# Ethernet_Sheet.net
KiCad netlist of a schematic drawn in Altium Designer
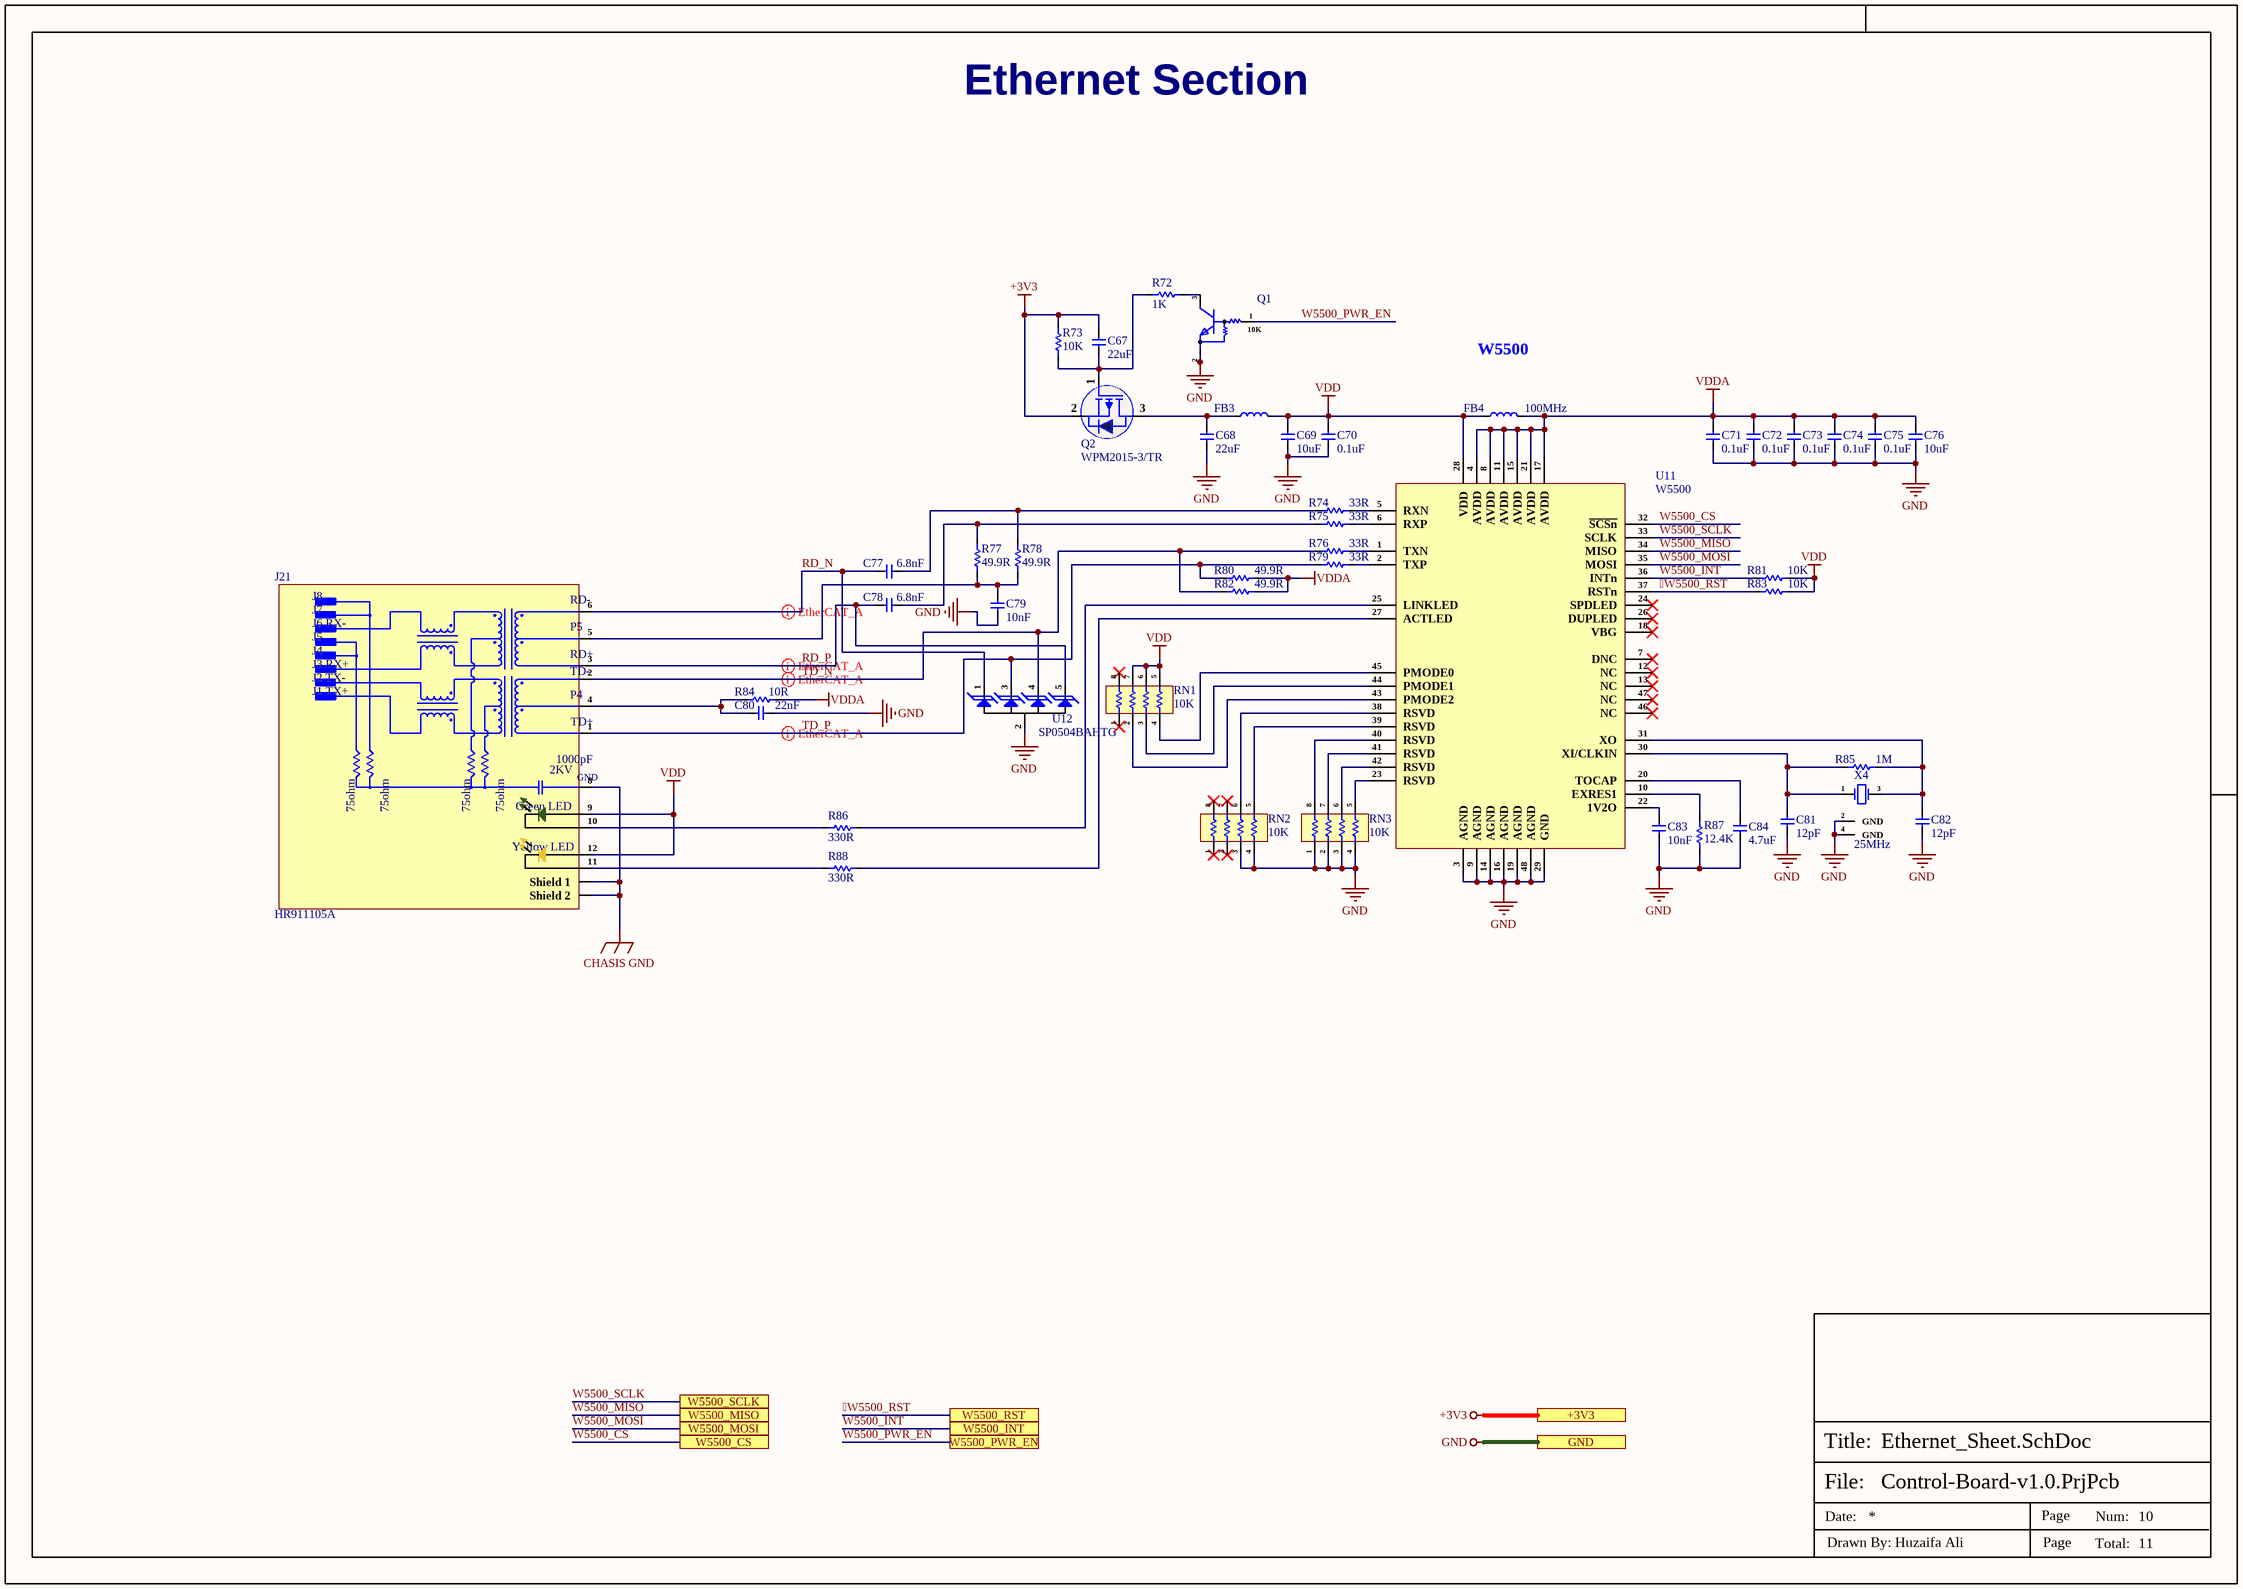
[diagram p0: Ethernet_Sheet.SchDoc]

(export (version "E")
  (design (tool "Eeschema 10.0.6"))
  (components
    (comp (ref "C67")
      (value "22uF")
      (footprint "Cap-0805")
      (description "CAP CER 22UF 35V X5R 0805")
      (fields
        (field (name "MANUFACTURER") "TDK Corporation")
        (field (name "MANUFACTURER PART NUMBER") "C2012X5R1V226MT000E")
      )
      (libsource (lib "eSpark Libraries") (part "C2012X5R1V226MT000E"))
    )
    (comp (ref "C68")
      (value "22uF")
      (footprint "Cap-0805")
      (description "CAP CER 22UF 25V X5R 0805")
      (fields
        (field (name "MANUFACTURER") "Yageo")
        (field (name "MANUFACTURER PART NUMBER") "CC0805MKX5R8BB226")
      )
      (libsource (lib "eSpark Libraries") (part "CC0805MKX5R8BB226"))
    )
    (comp (ref "C69")
      (value "10uF")
      (footprint "Cap-0603")
      (description "CAP CER 10UF 16V X5R 0603")
      (fields
        (field (name "MANUFACTURER") "Yageo")
        (field (name "MANUFACTURER PART NUMBER") "CC0603KRX5R7BB106")
      )
      (libsource (lib "eSpark Libraries") (part "CC0603KRX5R7BB106"))
    )
    (comp (ref "C70")
      (value "0.1uF")
      (footprint "Cap-0402")
      (description "CAP CER 0.1UF 50V X5R 0402")
      (fields
        (field (name "MANUFACTURER") "TDK")
        (field (name "MANUFACTURER PART NUMBER") "C1005X5R1H104K050BB")
      )
      (libsource (lib "eSpark Libraries") (part "C1005X5R1H104K050BB"))
    )
    (comp (ref "C71")
      (value "0.1uF")
      (footprint "Cap-0402")
      (description "CAP CER 0.1UF 50V X5R 0402")
      (fields
        (field (name "MANUFACTURER") "TDK")
        (field (name "MANUFACTURER PART NUMBER") "C1005X5R1H104K050BB")
      )
      (libsource (lib "eSpark Libraries") (part "C1005X5R1H104K050BB"))
    )
    (comp (ref "C72")
      (value "0.1uF")
      (footprint "Cap-0402")
      (description "CAP CER 0.1UF 50V X5R 0402")
      (fields
        (field (name "MANUFACTURER") "TDK")
        (field (name "MANUFACTURER PART NUMBER") "C1005X5R1H104K050BB")
      )
      (libsource (lib "eSpark Libraries") (part "C1005X5R1H104K050BB"))
    )
    (comp (ref "C73")
      (value "0.1uF")
      (footprint "Cap-0402")
      (description "CAP CER 0.1UF 50V X5R 0402")
      (fields
        (field (name "MANUFACTURER") "TDK")
        (field (name "MANUFACTURER PART NUMBER") "C1005X5R1H104K050BB")
      )
      (libsource (lib "eSpark Libraries") (part "C1005X5R1H104K050BB"))
    )
    (comp (ref "C74")
      (value "0.1uF")
      (footprint "Cap-0402")
      (description "CAP CER 0.1UF 50V X5R 0402")
      (fields
        (field (name "MANUFACTURER") "TDK")
        (field (name "MANUFACTURER PART NUMBER") "C1005X5R1H104K050BB")
      )
      (libsource (lib "eSpark Libraries") (part "C1005X5R1H104K050BB"))
    )
    (comp (ref "C75")
      (value "0.1uF")
      (footprint "Cap-0402")
      (description "CAP CER 0.1UF 50V X5R 0402")
      (fields
        (field (name "MANUFACTURER") "TDK")
        (field (name "MANUFACTURER PART NUMBER") "C1005X5R1H104K050BB")
      )
      (libsource (lib "eSpark Libraries") (part "C1005X5R1H104K050BB"))
    )
    (comp (ref "C76")
      (value "10uF")
      (footprint "Cap-0603")
      (description "CAP CER 10UF 16V X5R 0603")
      (fields
        (field (name "MANUFACTURER") "Yageo")
        (field (name "MANUFACTURER PART NUMBER") "CC0603KRX5R7BB106")
      )
      (libsource (lib "eSpark Libraries") (part "CC0603KRX5R7BB106"))
    )
    (comp (ref "C77")
      (value "6.8nF")
      (footprint "Cap-0603")
      (description "50V 6.8nF X7R ±10% 0603")
      (fields (field (name "MANUFACTURER") "FH") (field (name "MANUFACTURER PART NUMBER") "0603B682K500NT"))
      (libsource (lib "eSpark Libraries") (part "0603B682K500NT"))
    )
    (comp (ref "C78")
      (value "6.8nF")
      (footprint "Cap-0603")
      (description "50V 6.8nF X7R ±10% 0603")
      (fields (field (name "MANUFACTURER") "FH") (field (name "MANUFACTURER PART NUMBER") "0603B682K500NT"))
      (libsource (lib "eSpark Libraries") (part "0603B682K500NT"))
    )
    (comp (ref "C79")
      (value "10nF")
      (footprint "Cap-0603")
      (description "CAP CER 10000PF 50V C0G/NPO 0603")
      (fields
        (field (name "MANUFACTURER") "Yageo")
        (field (name "MANUFACTURER PART NUMBER") "CC0603JRNPO9BN103")
      )
      (libsource (lib "eSpark Libraries") (part "CC0603JRNPO9BN103"))
    )
    (comp (ref "C80")
      (value "22nF")
      (footprint "Cap-0603")
      (description "CAP CER 0.022UF 50V X7R 0603")
      (fields
        (field (name "MANUFACTURER") "Yageo")
        (field (name "MANUFACTURER PART NUMBER") "CC0603KRX7R9BB223")
      )
      (libsource (lib "eSpark Libraries") (part "CC0603KRX7R9BB223"))
    )
    (comp (ref "C81")
      (value "12pF")
      (footprint "Cap-0603")
      (description "CAP CER 12PF 50V C0G/NPO 0603")
      (fields
        (field (name "MANUFACTURER") "Yageo")
        (field (name "MANUFACTURER PART NUMBER") "CC0603J*NPO9B*120")
      )
      (libsource (lib "eSpark Libraries") (part "CC0603JRNPO9BN120"))
    )
    (comp (ref "C82")
      (value "12pF")
      (footprint "Cap-0603")
      (description "CAP CER 12PF 50V C0G/NPO 0603")
      (fields
        (field (name "MANUFACTURER") "Yageo")
        (field (name "MANUFACTURER PART NUMBER") "CC0603J*NPO9B*120")
      )
      (libsource (lib "eSpark Libraries") (part "CC0603JRNPO9BN120"))
    )
    (comp (ref "C83")
      (value "10nF")
      (footprint "Cap-0603")
      (description "CAP CER 10000PF 50V C0G/NPO 0603")
      (fields
        (field (name "MANUFACTURER") "Yageo")
        (field (name "MANUFACTURER PART NUMBER") "CC0603JRNPO9BN103")
      )
      (libsource (lib "eSpark Libraries") (part "CC0603JRNPO9BN103"))
    )
    (comp (ref "C84")
      (value "4.7uF")
      (footprint "Cap-0603")
      (description "CAP CER 4.7UF 10V X5R 0603")
      (fields
        (field (name "MANUFACTURER") "Yageo")
        (field (name "MANUFACTURER PART NUMBER") "CC0603KRX5R6BB475")
      )
      (libsource (lib "eSpark Libraries") (part "CC0603KRX5R6BB475"))
    )
    (comp (ref "FB3")
      (value "100MHz")
      (footprint "Ind-0805")
      (description "100mΩ ±25% 300Ω@100MHz 0805 Ferrite Beads ROHS")
      (fields
        (field (name "MANUFACTURER") "YJYCOIN")
        (field (name "MANUFACTURER PART NUMBER") "YI201209U301-2R0T")
      )
      (libsource (lib "eSpark Libraries") (part "YI201209U301-2R0T"))
    )
    (comp (ref "FB4")
      (value "100MHz")
      (footprint "Ind-0805")
      (description "100mΩ ±25% 300Ω@100MHz 0805 Ferrite Beads ROHS")
      (fields
        (field (name "MANUFACTURER") "YJYCOIN")
        (field (name "MANUFACTURER PART NUMBER") "YI201209U301-2R0T")
      )
      (libsource (lib "eSpark Libraries") (part "YI201209U301-2R0T"))
    )
    (comp (ref "J21")
      (value "HR911105A")
      (footprint "HR911105A")
      (description "RJ45 RJReceptacle 1 WithLED Plugin Ethernet Connectors/Modular Connectors (RJ45 RJ11) ROHS")
      (fields (field (name "MANUFACTURER") "HANRUN") (field (name "LCSC PART NUMBER") "C12074"))
      (libsource (lib "eSpark Libraries") (part "HR911105A"))
    )
    (comp (ref "Q1")
      (value "LMUN2211LT1G")
      (footprint "SOT-23")
      (description "NPN 246mW 100mA 50V SOT-23 Digital Transistors ROHS")
      (fields (field (name "MANUFACTURER") "LRC") (field (name "LCSC PART NUMBER") "C12775"))
      (libsource (lib "eSpark Libraries") (part "LMUN2211LT1G"))
    )
    (comp (ref "Q2")
      (value "WPM2015-3/TR")
      (footprint "Sot-23")
      (description "20V 2.2A 800mW 110mΩ@4.5V,2.7A 810mV@250uA P Channel SOT-23 MOSFETs ROHS")
      (fields (field (name "MANUFACTURER") "WILLSEMI") (field (name "LCSC PART NUMBER") "C213159"))
      (libsource (lib "eSpark Libraries") (part "WPM2015-3/TR"))
    )
    (comp (ref "R72")
      (value "1K")
      (footprint "Res-0402")
      (description "RES SMD 1K OHM 1% 1/5W 0402")
      (fields
        (field (name "MANUFACTURER") "Vishay Dale")
        (field (name "MANUFACTURER PART NUMBER") "CRCW04021K00FKEDHP")
      )
      (libsource (lib "eSpark Libraries") (part "CRCW04021K00FKEDHP"))
    )
    (comp (ref "R73")
      (value "10K")
      (footprint "Res-0402")
      (description "RES 10K OHM 1% 1/16W 0402")
      (fields
        (field (name "MANUFACTURER") "Yageo")
        (field (name "MANUFACTURER PART NUMBER") "RC0402FR-0710KL")
      )
      (libsource (lib "eSpark Libraries") (part "RC0402FR-0710KL"))
    )
    (comp (ref "R74")
      (value "33R")
      (footprint "Res-0402")
      (description "RES 33 OHM 1% 1/16W 0402")
      (fields
        (field (name "MANUFACTURER") "Yageo")
        (field (name "MANUFACTURER PART NUMBER") "RC0402FR-0733RL")
      )
      (libsource (lib "eSpark Libraries") (part "RC0402FR-0733RL"))
    )
    (comp (ref "R75")
      (value "33R")
      (footprint "Res-0402")
      (description "RES 33 OHM 1% 1/16W 0402")
      (fields
        (field (name "MANUFACTURER") "Yageo")
        (field (name "MANUFACTURER PART NUMBER") "RC0402FR-0733RL")
      )
      (libsource (lib "eSpark Libraries") (part "RC0402FR-0733RL"))
    )
    (comp (ref "R76")
      (value "33R")
      (footprint "Res-0402")
      (description "RES 33 OHM 1% 1/16W 0402")
      (fields
        (field (name "MANUFACTURER") "Yageo")
        (field (name "MANUFACTURER PART NUMBER") "RC0402FR-0733RL")
      )
      (libsource (lib "eSpark Libraries") (part "RC0402FR-0733RL"))
    )
    (comp (ref "R77")
      (value "49.9R")
      (footprint "Res-0603")
      (description "RES 49.9 OHM 1% 1/10W 0603")
      (fields
        (field (name "MANUFACTURER") "Yageo")
        (field (name "MANUFACTURER PART NUMBER") "RC0603FR-0749R9L")
      )
      (libsource (lib "eSpark Libraries") (part "RC0603FR-0749R9L"))
    )
    (comp (ref "R78")
      (value "49.9R")
      (footprint "Res-0603")
      (description "RES 49.9 OHM 1% 1/10W 0603")
      (fields
        (field (name "MANUFACTURER") "Yageo")
        (field (name "MANUFACTURER PART NUMBER") "RC0603FR-0749R9L")
      )
      (libsource (lib "eSpark Libraries") (part "RC0603FR-0749R9L"))
    )
    (comp (ref "R79")
      (value "33R")
      (footprint "Res-0402")
      (description "RES 33 OHM 1% 1/16W 0402")
      (fields
        (field (name "MANUFACTURER") "Yageo")
        (field (name "MANUFACTURER PART NUMBER") "RC0402FR-0733RL")
      )
      (libsource (lib "eSpark Libraries") (part "RC0402FR-0733RL"))
    )
    (comp (ref "R80")
      (value "49.9R")
      (footprint "Res-0603")
      (description "RES 49.9 OHM 1% 1/10W 0603")
      (fields
        (field (name "MANUFACTURER") "Yageo")
        (field (name "MANUFACTURER PART NUMBER") "RC0603FR-0749R9L")
      )
      (libsource (lib "eSpark Libraries") (part "RC0603FR-0749R9L"))
    )
    (comp (ref "R81")
      (value "10K")
      (footprint "Res-0402")
      (description "RES 10K OHM 1% 1/16W 0402")
      (fields
        (field (name "MANUFACTURER") "Yageo")
        (field (name "MANUFACTURER PART NUMBER") "RC0402FR-0710KL")
      )
      (libsource (lib "eSpark Libraries") (part "RC0402FR-0710KL"))
    )
    (comp (ref "R82")
      (value "49.9R")
      (footprint "Res-0603")
      (description "RES 49.9 OHM 1% 1/10W 0603")
      (fields
        (field (name "MANUFACTURER") "Yageo")
        (field (name "MANUFACTURER PART NUMBER") "RC0603FR-0749R9L")
      )
      (libsource (lib "eSpark Libraries") (part "RC0603FR-0749R9L"))
    )
    (comp (ref "R83")
      (value "10K")
      (footprint "Res-0402")
      (description "RES 10K OHM 1% 1/16W 0402")
      (fields
        (field (name "MANUFACTURER") "Yageo")
        (field (name "MANUFACTURER PART NUMBER") "RC0402FR-0710KL")
      )
      (libsource (lib "eSpark Libraries") (part "RC0402FR-0710KL"))
    )
    (comp (ref "R84")
      (value "10R")
      (footprint "Res-0402")
      (description "RES SMD 10 OHM 1% 1/5W 0402")
      (fields
        (field (name "MANUFACTURER") "Vishay Dale")
        (field (name "MANUFACTURER PART NUMBER") "CRCW040210R0FKEDHP")
      )
      (libsource (lib "eSpark Libraries") (part "CRCW040210R0FKEDHP"))
    )
    (comp (ref "R85")
      (value "1M")
      (footprint "Res-0402")
      (description "RES SMD 1M OHM 5% 1/16W 0402")
      (fields
        (field (name "MANUFACTURER") "Yageo")
        (field (name "MANUFACTURER PART NUMBER") "AF0402JR-071ML")
      )
      (libsource (lib "eSpark Libraries") (part "AF0402JR-071ML"))
    )
    (comp (ref "R86")
      (value "330R")
      (footprint "Res-0402")
      (description "SMD Chip Resistor, 330 Ohm, ± 1%, 63 mW, 0402 [1005 Metric], Thick Film, General Purpose")
      (fields
        (field (name "MANUFACTURER") "Vishay Semiconductors")
        (field (name "MANUFACTURER PART NUMBER") "CRCW0402330RFKEDC")
      )
      (libsource (lib "eSpark Libraries") (part "CRCW0402330RFKEDC"))
    )
    (comp (ref "R87")
      (value "12.4K")
      (footprint "Res-0603")
      (description "RES SMD 12.4K OHM 1% 1/10W 0603")
      (fields
        (field (name "MANUFACTURER") "Yageo")
        (field (name "MANUFACTURER PART NUMBER") "RC0603FR-0712K4L")
      )
      (libsource (lib "eSpark Libraries") (part "RC0603FR-0712K4L"))
    )
    (comp (ref "R88")
      (value "330R")
      (footprint "Res-0402")
      (description "SMD Chip Resistor, 330 Ohm, ± 1%, 63 mW, 0402 [1005 Metric], Thick Film, General Purpose")
      (fields
        (field (name "MANUFACTURER") "Vishay Semiconductors")
        (field (name "MANUFACTURER PART NUMBER") "CRCW0402330RFKEDC")
      )
      (libsource (lib "eSpark Libraries") (part "CRCW0402330RFKEDC"))
    )
    (comp (ref "RN1")
      (value "10K")
      (footprint "YC164-FR-0710KL")
      (description "RES ARRAY 4 RES 10K OHM 1206")
      (fields
        (field (name "MANUFACTURER") "Yageo")
        (field (name "MANUFACTURER PART NUMBER") "YC164-FR-0710KL")
      )
      (libsource (lib "eSpark Libraries") (part "YC164-FR-0710KL"))
    )
    (comp (ref "RN2")
      (value "10K")
      (footprint "YC164-FR-0710KL")
      (description "RES ARRAY 4 RES 10K OHM 1206")
      (fields
        (field (name "MANUFACTURER") "Yageo")
        (field (name "MANUFACTURER PART NUMBER") "YC164-FR-0710KL")
      )
      (libsource (lib "eSpark Libraries") (part "YC164-FR-0710KL"))
    )
    (comp (ref "RN3")
      (value "10K")
      (footprint "YC164-FR-0710KL")
      (description "RES ARRAY 4 RES 10K OHM 1206")
      (fields
        (field (name "MANUFACTURER") "Yageo")
        (field (name "MANUFACTURER PART NUMBER") "YC164-FR-0710KL")
      )
      (libsource (lib "eSpark Libraries") (part "YC164-FR-0710KL"))
    )
    (comp (ref "U11")
      (value "W5500")
      (footprint "48-LQFP (7x7)_")
      (description "SPI LQFP-48(7x7) Ethernet ICs ROHS")
      (fields (field (name "MANUFACTURER") "WIZNET") (field (name "LCSC PART NUMBER") "C32843"))
      (libsource (lib "eSpark Libraries") (part "W5500"))
    )
    (comp (ref "U12")
      (value "SP0504BAHTG")
      (footprint "SOT-23-5")
      (description "TVS DIODE 5.5VWM 8.5VC SOT23-5")
      (fields (field (name "MANUFACTURER") "Littelfuse") (field (name "LCSC PART NUMBER") "C10675"))
      (libsource (lib "eSpark Libraries") (part "SP0504BAHTG"))
    )
    (comp (ref "X4")
      (value "25MHz")
      (footprint "Q22FA12800090")
      (description "CRYSTAL 25.0000MHZ 12PF SMD")
      (fields
        (field (name "MANUFACTURER") "Seiko Epson")
        (field (name "MANUFACTURER PART NUMBER") "Q22FA12800090")
      )
      (libsource (lib "eSpark Libraries") (part "Q22FA12800090"))
    )
  )
  (nets
    (net (code "1") (name "+3V3") (class "Default")
      (node (ref "C67") (pin "2") (pinfunction "2_2") (pintype "passive"))
      (node (ref "Q2") (pin "2") (pinfunction "S_2") (pintype "passive"))
      (node (ref "R73") (pin "2") (pinfunction "2_2") (pintype "passive"))
    )
    (net (code "2") (name "/W5500_RST") (class "Default")
      (node (ref "R83") (pin "2") (pinfunction "2_2") (pintype "passive"))
      (node (ref "U11") (pin "37") (pinfunction "RSTn_37") (pintype "passive"))
    )
    (net (code "3") (name "/RD_N") (class "Default")
      (node (ref "C77") (pin "1") (pinfunction "1_1") (pintype "passive"))
      (node (ref "J21") (pin "6") (pinfunction "RD-_6") (pintype "passive"))
      (node (ref "U12") (pin "1") (pinfunction "K_1") (pintype "passive"))
    )
    (net (code "4") (name "/RD_P") (class "Default")
      (node (ref "C78") (pin "1") (pinfunction "1_1") (pintype "passive"))
      (node (ref "J21") (pin "3") (pinfunction "RD+_3") (pintype "passive"))
      (node (ref "U12") (pin "5") (pinfunction "K_5") (pintype "passive"))
    )
    (net (code "5") (name "/TD_N") (class "Default")
      (node (ref "J21") (pin "2") (pinfunction "TD-_2") (pintype "passive"))
      (node (ref "R76") (pin "1") (pinfunction "1_1") (pintype "passive"))
      (node (ref "R82") (pin "2") (pinfunction "2_2") (pintype "passive"))
      (node (ref "U12") (pin "4") (pinfunction "K_4") (pintype "passive"))
    )
    (net (code "6") (name "/TD_P") (class "Default")
      (node (ref "J21") (pin "1") (pinfunction "TD+_1") (pintype "passive"))
      (node (ref "R79") (pin "1") (pinfunction "1_1") (pintype "passive"))
      (node (ref "R80") (pin "2") (pinfunction "2_2") (pintype "passive"))
      (node (ref "U12") (pin "3") (pinfunction "K_3") (pintype "passive"))
    )
    (net (code "7") (name "/W5500_CS") (class "Default")
      (node (ref "U11") (pin "32") (pinfunction "~{SCSn}_32") (pintype "passive"))
    )
    (net (code "8") (name "/W5500_INT") (class "Default")
      (node (ref "R81") (pin "2") (pinfunction "2_2") (pintype "passive"))
      (node (ref "U11") (pin "36") (pinfunction "INTn_36") (pintype "passive"))
    )
    (net (code "9") (name "/W5500_MISO") (class "Default")
      (node (ref "U11") (pin "34") (pinfunction "MISO_34") (pintype "passive"))
    )
    (net (code "10") (name "/W5500_MOSI") (class "Default")
      (node (ref "U11") (pin "35") (pinfunction "MOSI_35") (pintype "passive"))
    )
    (net (code "11") (name "/W5500_PWR_EN") (class "Default")
      (node (ref "Q1") (pin "1") (pinfunction "B_1") (pintype "passive"))
    )
    (net (code "12") (name "/W5500_SCLK") (class "Default")
      (node (ref "U11") (pin "33") (pinfunction "SCLK_33") (pintype "passive"))
    )
    (net (code "13") (name "CHASIS GND") (class "Default")
      (node (ref "J21") (pin "8") (pinfunction "GND_8") (pintype "power_in"))
      (node (ref "J21") (pin "Shield_1") (pinfunction "Shield_1_Shield_1") (pintype "passive"))
      (node (ref "J21") (pin "Shield_2") (pinfunction "Shield_2_Shield_2") (pintype "passive"))
    )
    (net (code "14") (name "GND") (class "Default")
      (node (ref "C68") (pin "1") (pinfunction "1_1") (pintype "passive"))
      (node (ref "C69") (pin "1") (pinfunction "1_1") (pintype "passive"))
      (node (ref "C70") (pin "1") (pinfunction "1_1") (pintype "passive"))
      (node (ref "C71") (pin "1") (pinfunction "1_1") (pintype "passive"))
      (node (ref "C72") (pin "1") (pinfunction "1_1") (pintype "passive"))
      (node (ref "C73") (pin "1") (pinfunction "1_1") (pintype "passive"))
      (node (ref "C74") (pin "1") (pinfunction "1_1") (pintype "passive"))
      (node (ref "C75") (pin "1") (pinfunction "1_1") (pintype "passive"))
      (node (ref "C76") (pin "1") (pinfunction "1_1") (pintype "passive"))
      (node (ref "C79") (pin "1") (pinfunction "1_1") (pintype "passive"))
      (node (ref "C80") (pin "2") (pinfunction "2_2") (pintype "passive"))
      (node (ref "C81") (pin "1") (pinfunction "1_1") (pintype "passive"))
      (node (ref "C82") (pin "1") (pinfunction "1_1") (pintype "passive"))
      (node (ref "C83") (pin "1") (pinfunction "1_1") (pintype "passive"))
      (node (ref "C84") (pin "1") (pinfunction "1_1") (pintype "passive"))
      (node (ref "Q1") (pin "2") (pinfunction "E_2") (pintype "passive"))
      (node (ref "R87") (pin "1") (pinfunction "1_1") (pintype "passive"))
      (node (ref "RN2") (pin "3") (pintype "passive"))
      (node (ref "RN2") (pin "4") (pintype "passive"))
      (node (ref "RN3") (pin "1") (pintype "passive"))
      (node (ref "RN3") (pin "2") (pintype "passive"))
      (node (ref "RN3") (pin "3") (pintype "passive"))
      (node (ref "RN3") (pin "4") (pintype "passive"))
      (node (ref "U11") (pin "14") (pinfunction "AGND_14") (pintype "passive"))
      (node (ref "U11") (pin "16") (pinfunction "AGND_16") (pintype "passive"))
      (node (ref "U11") (pin "19") (pinfunction "AGND_19") (pintype "passive"))
      (node (ref "U11") (pin "29") (pinfunction "GND_29") (pintype "passive"))
      (node (ref "U11") (pin "3") (pinfunction "AGND_3") (pintype "passive"))
      (node (ref "U11") (pin "48") (pinfunction "AGND_48") (pintype "passive"))
      (node (ref "U11") (pin "9") (pinfunction "AGND_9") (pintype "passive"))
      (node (ref "U12") (pin "2") (pinfunction "A_2") (pintype "passive"))
      (node (ref "X4") (pin "2") (pinfunction "GND_2") (pintype "passive"))
      (node (ref "X4") (pin "4") (pinfunction "GND_4") (pintype "passive"))
    )
    (net (code "15") (name "Net-(C77-Pad2)") (class "Default")
      (node (ref "C77") (pin "2") (pinfunction "2_2") (pintype "passive"))
      (node (ref "R74") (pin "1") (pinfunction "1_1") (pintype "passive"))
      (node (ref "R78") (pin "2") (pinfunction "2_2") (pintype "passive"))
    )
    (net (code "16") (name "Net-(C78-Pad2)") (class "Default")
      (node (ref "C78") (pin "2") (pinfunction "2_2") (pintype "passive"))
      (node (ref "R75") (pin "1") (pinfunction "1_1") (pintype "passive"))
      (node (ref "R77") (pin "2") (pinfunction "2_2") (pintype "passive"))
    )
    (net (code "17") (name "Net-(J21-CATHODE-Pad10)") (class "Default")
      (node (ref "J21") (pin "10") (pinfunction "CATHODE_10") (pintype "passive"))
      (node (ref "R86") (pin "1") (pinfunction "1_1") (pintype "passive"))
    )
    (net (code "18") (name "Net-(J21-CATHODE-Pad11)") (class "Default")
      (node (ref "J21") (pin "11") (pinfunction "CATHODE_11") (pintype "passive"))
      (node (ref "R88") (pin "1") (pinfunction "1_1") (pintype "passive"))
    )
    (net (code "19") (name "Net-(J21-P4)") (class "Default")
      (node (ref "C80") (pin "1") (pinfunction "1_1") (pintype "passive"))
      (node (ref "J21") (pin "4") (pinfunction "P4_4") (pintype "passive"))
      (node (ref "R84") (pin "1") (pinfunction "1_1") (pintype "passive"))
    )
    (net (code "20") (name "Net-(J21-P5)") (class "Default")
      (node (ref "C79") (pin "2") (pinfunction "2_2") (pintype "passive"))
      (node (ref "J21") (pin "5") (pinfunction "P5_5") (pintype "passive"))
      (node (ref "R77") (pin "1") (pinfunction "1_1") (pintype "passive"))
      (node (ref "R78") (pin "1") (pinfunction "1_1") (pintype "passive"))
    )
    (net (code "21") (name "Net-(Q1-C)") (class "Default")
      (node (ref "Q1") (pin "3") (pinfunction "C_3") (pintype "passive"))
      (node (ref "R72") (pin "2") (pinfunction "2_2") (pintype "passive"))
    )
    (net (code "22") (name "Net-(Q2-D)") (class "Default")
      (node (ref "C68") (pin "2") (pinfunction "2_2") (pintype "passive"))
      (node (ref "FB3") (pin "1") (pinfunction "1_1") (pintype "passive"))
      (node (ref "Q2") (pin "3") (pinfunction "D_3") (pintype "passive"))
    )
    (net (code "23") (name "Net-(Q2-G)") (class "Default")
      (node (ref "C67") (pin "1") (pinfunction "1_1") (pintype "passive"))
      (node (ref "Q2") (pin "1") (pinfunction "G_1") (pintype "passive"))
      (node (ref "R72") (pin "1") (pinfunction "1_1") (pintype "passive"))
      (node (ref "R73") (pin "1") (pinfunction "1_1") (pintype "passive"))
    )
    (net (code "24") (name "Net-(RN2-Pad5)") (class "Default")
      (node (ref "RN2") (pin "5") (pintype "passive"))
      (node (ref "U11") (pin "39") (pinfunction "RSVD_39") (pintype "passive"))
    )
    (net (code "25") (name "Net-(RN2-Pad6)") (class "Default")
      (node (ref "RN2") (pin "6") (pintype "passive"))
      (node (ref "U11") (pin "38") (pinfunction "RSVD_38") (pintype "passive"))
    )
    (net (code "26") (name "Net-(RN3-Pad5)") (class "Default")
      (node (ref "RN3") (pin "5") (pintype "passive"))
      (node (ref "U11") (pin "23") (pinfunction "RSVD_23") (pintype "passive"))
    )
    (net (code "27") (name "Net-(RN3-Pad6)") (class "Default")
      (node (ref "RN3") (pin "6") (pintype "passive"))
      (node (ref "U11") (pin "42") (pinfunction "RSVD_42") (pintype "passive"))
    )
    (net (code "28") (name "Net-(RN3-Pad7)") (class "Default")
      (node (ref "RN3") (pin "7") (pintype "passive"))
      (node (ref "U11") (pin "41") (pinfunction "RSVD_41") (pintype "passive"))
    )
    (net (code "29") (name "Net-(RN3-Pad8)") (class "Default")
      (node (ref "RN3") (pin "8") (pintype "passive"))
      (node (ref "U11") (pin "40") (pinfunction "RSVD_40") (pintype "passive"))
    )
    (net (code "30") (name "Net-(U11-1V2O)") (class "Default")
      (node (ref "C83") (pin "2") (pinfunction "2_2") (pintype "passive"))
      (node (ref "U11") (pin "22") (pinfunction "1V2O_22") (pintype "passive"))
    )
    (net (code "31") (name "Net-(U11-ACTLED)") (class "Default")
      (node (ref "R88") (pin "2") (pinfunction "2_2") (pintype "passive"))
      (node (ref "U11") (pin "27") (pinfunction "ACTLED_27") (pintype "passive"))
    )
    (net (code "32") (name "Net-(U11-EXRES1)") (class "Default")
      (node (ref "R87") (pin "2") (pinfunction "2_2") (pintype "passive"))
      (node (ref "U11") (pin "10") (pinfunction "EXRES1_10") (pintype "passive"))
    )
    (net (code "33") (name "Net-(U11-LINKLED)") (class "Default")
      (node (ref "R86") (pin "2") (pinfunction "2_2") (pintype "passive"))
      (node (ref "U11") (pin "25") (pinfunction "LINKLED_25") (pintype "passive"))
    )
    (net (code "34") (name "Net-(U11-PMODE0)") (class "Default")
      (node (ref "RN1") (pin "4") (pintype "passive"))
      (node (ref "U11") (pin "45") (pinfunction "PMODE0_45") (pintype "passive"))
    )
    (net (code "35") (name "Net-(U11-PMODE1)") (class "Default")
      (node (ref "RN1") (pin "3") (pintype "passive"))
      (node (ref "U11") (pin "44") (pinfunction "PMODE1_44") (pintype "passive"))
    )
    (net (code "36") (name "Net-(U11-PMODE2)") (class "Default")
      (node (ref "RN1") (pin "2") (pintype "passive"))
      (node (ref "U11") (pin "43") (pinfunction "PMODE2_43") (pintype "passive"))
    )
    (net (code "37") (name "Net-(U11-RXN)") (class "Default")
      (node (ref "R74") (pin "2") (pinfunction "2_2") (pintype "passive"))
      (node (ref "U11") (pin "5") (pinfunction "RXN_5") (pintype "passive"))
    )
    (net (code "38") (name "Net-(U11-RXP)") (class "Default")
      (node (ref "R75") (pin "2") (pinfunction "2_2") (pintype "passive"))
      (node (ref "U11") (pin "6") (pinfunction "RXP_6") (pintype "passive"))
    )
    (net (code "39") (name "Net-(U11-TOCAP)") (class "Default")
      (node (ref "C84") (pin "2") (pinfunction "2_2") (pintype "passive"))
      (node (ref "U11") (pin "20") (pinfunction "TOCAP_20") (pintype "passive"))
    )
    (net (code "40") (name "Net-(U11-TXN)") (class "Default")
      (node (ref "R76") (pin "2") (pinfunction "2_2") (pintype "passive"))
      (node (ref "U11") (pin "1") (pinfunction "TXN_1") (pintype "passive"))
    )
    (net (code "41") (name "Net-(U11-TXP)") (class "Default")
      (node (ref "R79") (pin "2") (pinfunction "2_2") (pintype "passive"))
      (node (ref "U11") (pin "2") (pinfunction "TXP_2") (pintype "passive"))
    )
    (net (code "42") (name "Net-(U11-XI{slash}CLKIN)") (class "Default")
      (node (ref "C81") (pin "2") (pinfunction "2_2") (pintype "passive"))
      (node (ref "R85") (pin "1") (pinfunction "1_1") (pintype "passive"))
      (node (ref "U11") (pin "30") (pinfunction "XI/CLKIN_30") (pintype "passive"))
      (node (ref "X4") (pin "1") (pinfunction "OSC1_1") (pintype "passive"))
    )
    (net (code "43") (name "Net-(U11-XO)") (class "Default")
      (node (ref "C82") (pin "2") (pinfunction "2_2") (pintype "passive"))
      (node (ref "R85") (pin "2") (pinfunction "2_2") (pintype "passive"))
      (node (ref "U11") (pin "31") (pinfunction "XO_31") (pintype "passive"))
      (node (ref "X4") (pin "3") (pinfunction "OSC2_3") (pintype "passive"))
    )
    (net (code "44") (name "VDD") (class "Default")
      (node (ref "C69") (pin "2") (pinfunction "2_2") (pintype "passive"))
      (node (ref "C70") (pin "2") (pinfunction "2_2") (pintype "passive"))
      (node (ref "FB3") (pin "2") (pinfunction "2_2") (pintype "passive"))
      (node (ref "FB4") (pin "1") (pinfunction "1_1") (pintype "passive"))
      (node (ref "J21") (pin "12") (pinfunction "ANODE_12") (pintype "passive"))
      (node (ref "J21") (pin "9") (pinfunction "ANODE_9") (pintype "passive"))
      (node (ref "R81") (pin "1") (pinfunction "1_1") (pintype "passive"))
      (node (ref "R83") (pin "1") (pinfunction "1_1") (pintype "passive"))
      (node (ref "RN1") (pin "5") (pintype "passive"))
      (node (ref "RN1") (pin "6") (pintype "passive"))
      (node (ref "RN1") (pin "7") (pintype "passive"))
      (node (ref "U11") (pin "28") (pinfunction "VDD_28") (pintype "passive"))
    )
    (net (code "45") (name "VDDA") (class "Default")
      (node (ref "C71") (pin "2") (pinfunction "2_2") (pintype "passive"))
      (node (ref "C72") (pin "2") (pinfunction "2_2") (pintype "passive"))
      (node (ref "C73") (pin "2") (pinfunction "2_2") (pintype "passive"))
      (node (ref "C74") (pin "2") (pinfunction "2_2") (pintype "passive"))
      (node (ref "C75") (pin "2") (pinfunction "2_2") (pintype "passive"))
      (node (ref "C76") (pin "2") (pinfunction "2_2") (pintype "passive"))
      (node (ref "FB4") (pin "2") (pinfunction "2_2") (pintype "passive"))
      (node (ref "R80") (pin "1") (pinfunction "1_1") (pintype "passive"))
      (node (ref "R82") (pin "1") (pinfunction "1_1") (pintype "passive"))
      (node (ref "R84") (pin "2") (pinfunction "2_2") (pintype "passive"))
      (node (ref "U11") (pin "11") (pinfunction "AVDD_11") (pintype "passive"))
      (node (ref "U11") (pin "15") (pinfunction "AVDD_15") (pintype "passive"))
      (node (ref "U11") (pin "17") (pinfunction "AVDD_17") (pintype "passive"))
      (node (ref "U11") (pin "21") (pinfunction "AVDD_21") (pintype "passive"))
      (node (ref "U11") (pin "4") (pinfunction "AVDD_4") (pintype "passive"))
      (node (ref "U11") (pin "8") (pinfunction "AVDD_8") (pintype "passive"))
    )
    (net (code "46") (name "unconnected-(RN1-Pad1)") (class "Default")
      (node (ref "RN1") (pin "1") (pintype "passive+no_connect"))
    )
    (net (code "47") (name "unconnected-(RN1-Pad8)") (class "Default")
      (node (ref "RN1") (pin "8") (pintype "passive+no_connect"))
    )
    (net (code "48") (name "unconnected-(RN2-Pad1)") (class "Default")
      (node (ref "RN2") (pin "1") (pintype "passive+no_connect"))
    )
    (net (code "49") (name "unconnected-(RN2-Pad2)") (class "Default")
      (node (ref "RN2") (pin "2") (pintype "passive+no_connect"))
    )
    (net (code "50") (name "unconnected-(RN2-Pad7)") (class "Default")
      (node (ref "RN2") (pin "7") (pintype "passive+no_connect"))
    )
    (net (code "51") (name "unconnected-(RN2-Pad8)") (class "Default")
      (node (ref "RN2") (pin "8") (pintype "passive+no_connect"))
    )
    (net (code "52") (name "unconnected-(U11-DNC-Pad7)") (class "Default")
      (node (ref "U11") (pin "7") (pinfunction "DNC_7") (pintype "passive+no_connect"))
    )
    (net (code "53") (name "unconnected-(U11-DUPLED-Pad26)") (class "Default")
      (node (ref "U11") (pin "26") (pinfunction "DUPLED_26") (pintype "passive+no_connect"))
    )
    (net (code "54") (name "unconnected-(U11-NC-Pad12)") (class "Default")
      (node (ref "U11") (pin "12") (pinfunction "NC_12") (pintype "passive+no_connect"))
    )
    (net (code "55") (name "unconnected-(U11-NC-Pad13)") (class "Default")
      (node (ref "U11") (pin "13") (pinfunction "NC_13") (pintype "passive+no_connect"))
    )
    (net (code "56") (name "unconnected-(U11-NC-Pad46)") (class "Default")
      (node (ref "U11") (pin "46") (pinfunction "NC_46") (pintype "passive+no_connect"))
    )
    (net (code "57") (name "unconnected-(U11-NC-Pad47)") (class "Default")
      (node (ref "U11") (pin "47") (pinfunction "NC_47") (pintype "passive+no_connect"))
    )
    (net (code "58") (name "unconnected-(U11-SPDLED-Pad24)") (class "Default")
      (node (ref "U11") (pin "24") (pinfunction "SPDLED_24") (pintype "passive+no_connect"))
    )
    (net (code "59") (name "unconnected-(U11-VBG-Pad18)") (class "Default")
      (node (ref "U11") (pin "18") (pinfunction "VBG_18") (pintype "passive+no_connect"))
    )
  )
)
